# i2c-pressure-driver.net
KiCad netlist of a schematic drawn in EAGLE
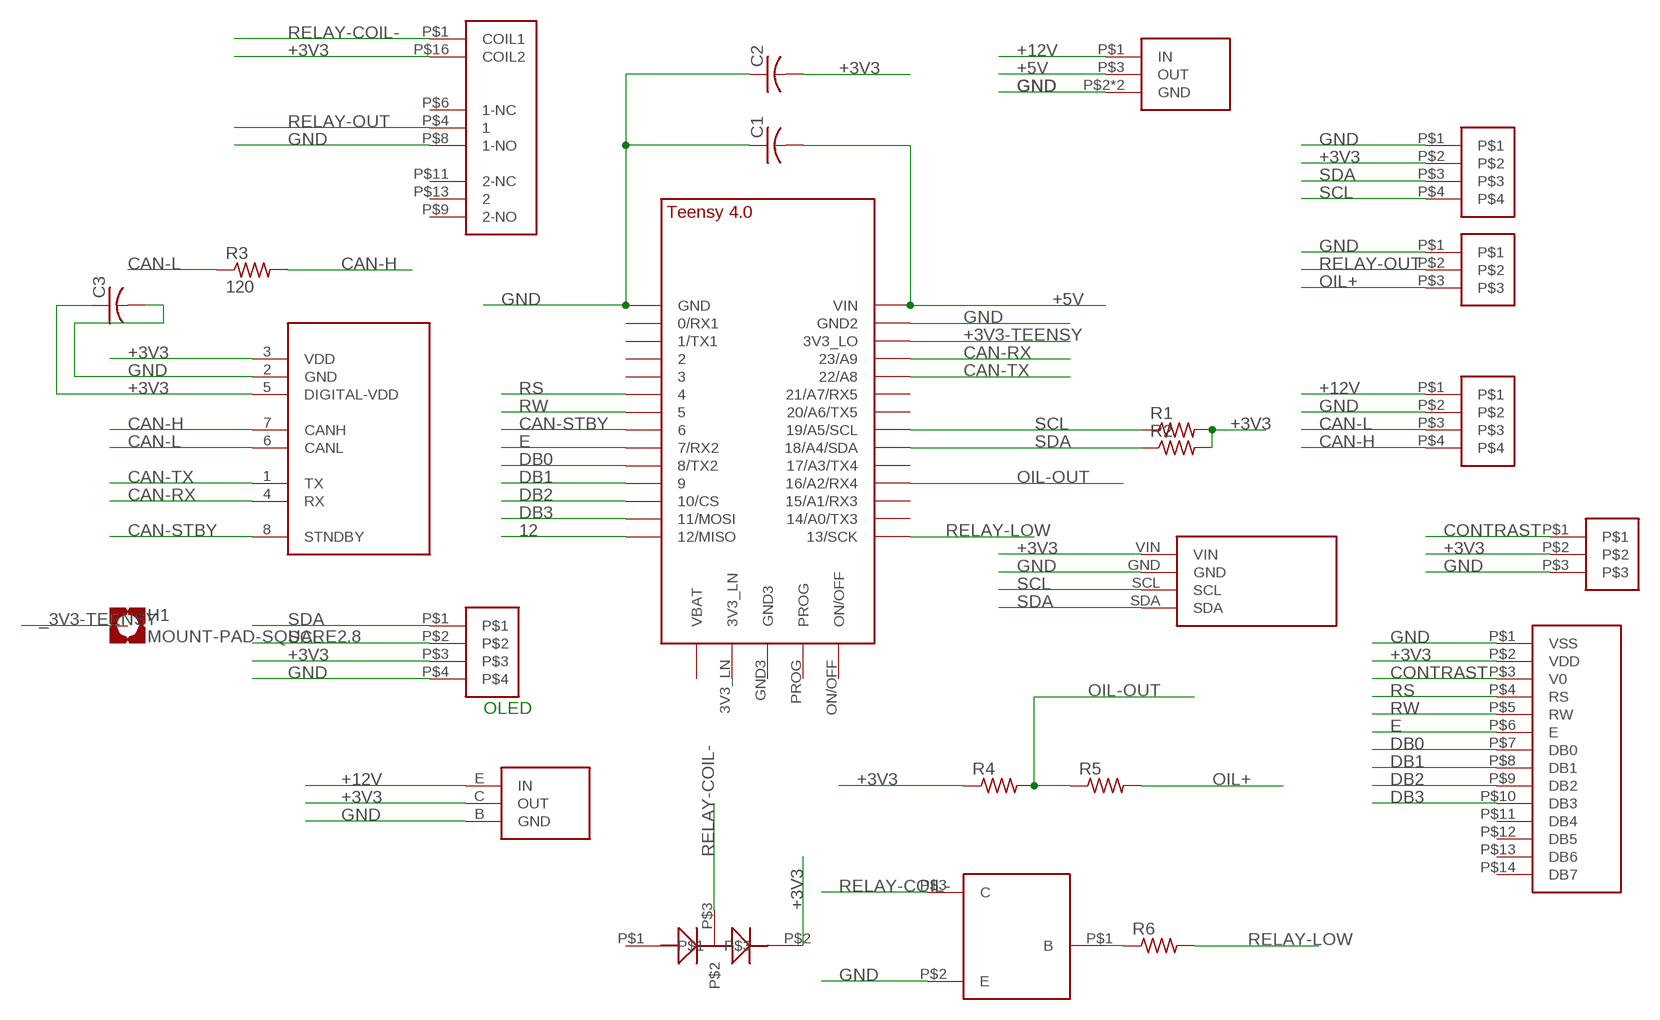
[diagram p0: schematic, sheet 1]

(export (version "E")
  (design (tool "Eeschema 10.0.6"))
  (components
    (comp (ref "C1")
      (value "C-USC1210K")
      (footprint "eagle-import:C1210K")
      (libsource (lib "eagle-import") (part "C-USC1210K"))
    )
    (comp (ref "C2")
      (value "C-USC1210K")
      (footprint "eagle-import:C1210K")
      (libsource (lib "eagle-import") (part "C-USC1210K"))
    )
    (comp (ref "C3")
      (value "C-USC0603K")
      (footprint "eagle-import:C0603K")
      (libsource (lib "eagle-import") (part "C-USC0603K"))
    )
    (comp (ref "H1")
      (value "MOUNT-PAD-SQUARE2.8")
      (footprint "eagle-import:2,8-PAD-SQUARE")
      (libsource (lib "eagle-import") (part "MOUNT-PAD-SQUARE2.8"))
    )
    (comp (ref "R1")
      (value "R-US_R0805")
      (footprint "eagle-import:R0805")
      (libsource (lib "eagle-import") (part "R-US_R0805"))
    )
    (comp (ref "R2")
      (value "R-US_R0805")
      (footprint "eagle-import:R0805")
      (libsource (lib "eagle-import") (part "R-US_R0805"))
    )
    (comp (ref "R3")
      (value "120")
      (footprint "eagle-import:R0805W")
      (libsource (lib "eagle-import") (part "R-US_R0805W"))
    )
    (comp (ref "R4")
      (value "R-US_M0805")
      (footprint "eagle-import:M0805")
      (libsource (lib "eagle-import") (part "R-US_M0805"))
    )
    (comp (ref "R5")
      (value "R-US_M0805")
      (footprint "eagle-import:M0805")
      (libsource (lib "eagle-import") (part "R-US_M0805"))
    )
    (comp (ref "R6")
      (value "R-US_R0805")
      (footprint "eagle-import:R0805")
      (libsource (lib "eagle-import") (part "R-US_R0805"))
    )
    (comp (ref "U$1")
      (value "TEENSY_4.0")
      (footprint "eagle-import:TEENSY_4.0")
      (libsource (lib "eagle-import") (part "TEENSY_4.0"))
    )
    (comp (ref "U$2")
      (value "NEWHAVEN-LCD-8X2")
      (footprint "eagle-import:NEWHAVEN-8X2-LCD")
      (libsource (lib "eagle-import") (part "NEWHAVEN-LCD-8X2"))
    )
    (comp (ref "U$3")
      (value "LDO-3.3V-AZ1117CR-3.3TRG1")
      (footprint "eagle-import:SOT89-BCE")
      (libsource (lib "eagle-import") (part "LDO-3.3V-AZ1117CR-3.3TRG1"))
    )
    (comp (ref "U$4")
      (value "1X4-1725672")
      (footprint "eagle-import:1X4-1725672")
      (libsource (lib "eagle-import") (part "1X4-1725672"))
    )
    (comp (ref "U$5")
      (value "1X3-1725669")
      (footprint "eagle-import:1X3-1725669")
      (libsource (lib "eagle-import") (part "1X3-1725669"))
    )
    (comp (ref "U$6")
      (value "1X4-1725672")
      (footprint "eagle-import:1X4-1725672")
      (libsource (lib "eagle-import") (part "1X4-1725672"))
    )
    (comp (ref "U$7")
      (value "MCP2562FD-CAN-TRANCIEVER")
      (footprint "eagle-import:SOIC8")
      (libsource (lib "eagle-import") (part "MCP2562FD-CAN-TRANCIEVER"))
    )
    (comp (ref "U$8")
      (value "TC33X-2-102E-POT")
      (footprint "eagle-import:TC33-X-2")
      (libsource (lib "eagle-import") (part "TC33X-2-102E-POT"))
    )
    (comp (ref "U$9")
      (value "1X4-1725672")
      (footprint "eagle-import:1X4-1725672")
      (libsource (lib "eagle-import") (part "1X4-1725672"))
    )
    (comp (ref "U$10")
      (value "LDO-5V-AZ1117CH2-5.0TRG1")
      (footprint "eagle-import:SOT-223")
      (libsource (lib "eagle-import") (part "LDO-5V-AZ1117CH2-5.0TRG1"))
    )
    (comp (ref "U$11")
      (value "BMP180-BREKOUT")
      (footprint "eagle-import:BMP180-BOARD")
      (libsource (lib "eagle-import") (part "BMP180-BREKOUT"))
    )
    (comp (ref "U$12")
      (value "RELAY-AMAZON")
      (footprint "eagle-import:RELAY-3V-AMAZON")
      (libsource (lib "eagle-import") (part "RELAY-AMAZON"))
    )
    (comp (ref "U$13")
      (value "NPN-GENERAL")
      (footprint "eagle-import:SOT23")
      (libsource (lib "eagle-import") (part "NPN-GENERAL"))
    )
    (comp (ref "U$14")
      (value "DIODE-MMBD4148SE")
      (footprint "eagle-import:SOT23")
      (libsource (lib "eagle-import") (part "DIODE-MMBD4148SE"))
    )
  )
  (nets
    (net (code "1") (name "/+3V3") (class "Default")
      (node (ref "C2") (pin "2") (pinfunction "2_2") (pintype "passive"))
      (node (ref "C3") (pin "1") (pinfunction "1_1") (pintype "passive"))
      (node (ref "R1") (pin "2") (pinfunction "2_2") (pintype "passive"))
      (node (ref "R2") (pin "2") (pinfunction "2_2") (pintype "passive"))
      (node (ref "R4") (pin "1") (pinfunction "1_1") (pintype "passive"))
      (node (ref "U$11") (pin "VIN") (pinfunction "VIN_VIN") (pintype "bidirectional"))
      (node (ref "U$12") (pin "P$16") (pinfunction "COIL2_P$16") (pintype "bidirectional"))
      (node (ref "U$14") (pin "P$2") (pinfunction "P$3_P$2") (pintype "bidirectional"))
      (node (ref "U$2") (pin "P$2") (pinfunction "VDD_P$2") (pintype "bidirectional"))
      (node (ref "U$3") (pin "C") (pinfunction "OUT_C") (pintype "bidirectional"))
      (node (ref "U$4") (pin "P$2") (pinfunction "P$2_P$2") (pintype "bidirectional"))
      (node (ref "U$7") (pin "3") (pinfunction "VDD_3") (pintype "bidirectional"))
      (node (ref "U$7") (pin "5") (pinfunction "DIGITAL-VDD_5") (pintype "bidirectional"))
      (node (ref "U$8") (pin "P$2") (pinfunction "P$2_P$2") (pintype "bidirectional"))
      (node (ref "U$9") (pin "P$3") (pinfunction "P$3_P$3") (pintype "bidirectional"))
    )
    (net (code "2") (name "/+3V3-TEENSY") (class "Default")
      (node (ref "U$1") (pin "3V3_LO") (pinfunction "3V3_LO_3V3_LO") (pintype "bidirectional"))
    )
    (net (code "3") (name "/+5V") (class "Default")
      (node (ref "C1") (pin "2") (pinfunction "2_2") (pintype "passive"))
      (node (ref "U$1") (pin "VIN") (pinfunction "VIN_VIN") (pintype "bidirectional"))
      (node (ref "U$10") (pin "P$3") (pinfunction "OUT_P$3") (pintype "bidirectional"))
    )
    (net (code "4") (name "/+12V") (class "Default")
      (node (ref "U$10") (pin "P$1") (pinfunction "IN_P$1") (pintype "bidirectional"))
      (node (ref "U$3") (pin "E") (pinfunction "IN_E") (pintype "bidirectional"))
      (node (ref "U$6") (pin "P$1") (pinfunction "P$1_P$1") (pintype "bidirectional"))
    )
    (net (code "5") (name "/12") (class "Default")
      (node (ref "U$1") (pin "12/MISO") (pinfunction "12/MISO_12/MISO") (pintype "bidirectional"))
    )
    (net (code "6") (name "/CAN-H") (class "Default")
      (node (ref "R3") (pin "2") (pinfunction "2_2") (pintype "passive"))
      (node (ref "U$6") (pin "P$4") (pinfunction "P$4_P$4") (pintype "bidirectional"))
      (node (ref "U$7") (pin "7") (pinfunction "CANH_7") (pintype "bidirectional"))
    )
    (net (code "7") (name "/CAN-L") (class "Default")
      (node (ref "R3") (pin "1") (pinfunction "1_1") (pintype "passive"))
      (node (ref "U$6") (pin "P$3") (pinfunction "P$3_P$3") (pintype "bidirectional"))
      (node (ref "U$7") (pin "6") (pinfunction "CANL_6") (pintype "bidirectional"))
    )
    (net (code "8") (name "/CAN-RX") (class "Default")
      (node (ref "U$1") (pin "23/A9") (pinfunction "23/A9_23/A9") (pintype "bidirectional"))
      (node (ref "U$7") (pin "4") (pinfunction "RX_4") (pintype "bidirectional"))
    )
    (net (code "9") (name "/CAN-STBY") (class "Default")
      (node (ref "U$1") (pin "6") (pinfunction "6_6") (pintype "bidirectional"))
      (node (ref "U$7") (pin "8") (pinfunction "STNDBY_8") (pintype "bidirectional"))
    )
    (net (code "10") (name "/CAN-TX") (class "Default")
      (node (ref "U$1") (pin "22/A8") (pinfunction "22/A8_22/A8") (pintype "bidirectional"))
      (node (ref "U$7") (pin "1") (pinfunction "TX_1") (pintype "bidirectional"))
    )
    (net (code "11") (name "/CONTRAST") (class "Default")
      (node (ref "U$2") (pin "P$3") (pinfunction "V0_P$3") (pintype "bidirectional"))
      (node (ref "U$8") (pin "P$1") (pinfunction "P$1_P$1") (pintype "bidirectional"))
    )
    (net (code "12") (name "/DB0") (class "Default")
      (node (ref "U$1") (pin "8") (pinfunction "8/TX2_8") (pintype "bidirectional"))
      (node (ref "U$2") (pin "P$7") (pinfunction "DB0_P$7") (pintype "bidirectional"))
    )
    (net (code "13") (name "/DB1") (class "Default")
      (node (ref "U$1") (pin "9/CS") (pinfunction "9_9/CS") (pintype "bidirectional"))
      (node (ref "U$2") (pin "P$8") (pinfunction "DB1_P$8") (pintype "bidirectional"))
    )
    (net (code "14") (name "/DB2") (class "Default")
      (node (ref "U$1") (pin "10/CS") (pinfunction "10/CS_10/CS") (pintype "bidirectional"))
      (node (ref "U$2") (pin "P$9") (pinfunction "DB2_P$9") (pintype "bidirectional"))
    )
    (net (code "15") (name "/DB3") (class "Default")
      (node (ref "U$1") (pin "11/MOSI") (pinfunction "11/MOSI_11/MOSI") (pintype "bidirectional"))
      (node (ref "U$2") (pin "P$10") (pinfunction "DB3_P$10") (pintype "bidirectional"))
    )
    (net (code "16") (name "/E") (class "Default")
      (node (ref "U$1") (pin "7") (pinfunction "7/RX2_7") (pintype "bidirectional"))
      (node (ref "U$2") (pin "P$6") (pinfunction "E_P$6") (pintype "bidirectional"))
    )
    (net (code "17") (name "/GND") (class "Default")
      (node (ref "C1") (pin "1") (pinfunction "1_1") (pintype "passive"))
      (node (ref "C2") (pin "1") (pinfunction "1_1") (pintype "passive"))
      (node (ref "C3") (pin "2") (pinfunction "2_2") (pintype "passive"))
      (node (ref "U$1") (pin "GND") (pinfunction "GND_GND") (pintype "bidirectional"))
      (node (ref "U$1") (pin "GND2") (pinfunction "GND2_GND2") (pintype "bidirectional"))
      (node (ref "U$10") (pin "P$2") (pinfunction "GND_P$2") (pintype "bidirectional"))
      (node (ref "U$10") (pin "PAD") (pinfunction "GND_PAD") (pintype "bidirectional"))
      (node (ref "U$11") (pin "GND") (pinfunction "GND_GND") (pintype "bidirectional"))
      (node (ref "U$12") (pin "P$8") (pinfunction "1-NO_P$8") (pintype "bidirectional"))
      (node (ref "U$13") (pin "P$2") (pinfunction "E_P$2") (pintype "bidirectional"))
      (node (ref "U$2") (pin "P$1") (pinfunction "VSS_P$1") (pintype "bidirectional"))
      (node (ref "U$3") (pin "B") (pinfunction "GND_B") (pintype "bidirectional"))
      (node (ref "U$4") (pin "P$1") (pinfunction "P$1_P$1") (pintype "bidirectional"))
      (node (ref "U$5") (pin "P$1") (pinfunction "P$1_P$1") (pintype "bidirectional"))
      (node (ref "U$6") (pin "P$2") (pinfunction "P$2_P$2") (pintype "bidirectional"))
      (node (ref "U$7") (pin "2") (pinfunction "GND_2") (pintype "bidirectional"))
      (node (ref "U$8") (pin "P$3") (pinfunction "P$3_P$3") (pintype "bidirectional"))
      (node (ref "U$9") (pin "P$4") (pinfunction "P$4_P$4") (pintype "bidirectional"))
    )
    (net (code "18") (name "/OIL+") (class "Default")
      (node (ref "R5") (pin "2") (pinfunction "2_2") (pintype "passive"))
      (node (ref "U$5") (pin "P$3") (pinfunction "P$3_P$3") (pintype "bidirectional"))
    )
    (net (code "19") (name "/OIL-OUT") (class "Default")
      (node (ref "R4") (pin "2") (pinfunction "2_2") (pintype "passive"))
      (node (ref "R5") (pin "1") (pinfunction "1_1") (pintype "passive"))
      (node (ref "U$1") (pin "16/A2") (pinfunction "16/A2/RX4_16/A2") (pintype "bidirectional"))
    )
    (net (code "20") (name "/RELAY-COIL-") (class "Default")
      (node (ref "U$12") (pin "P$1") (pinfunction "COIL1_P$1") (pintype "bidirectional"))
      (node (ref "U$13") (pin "P$3") (pinfunction "C_P$3") (pintype "bidirectional"))
      (node (ref "U$14") (pin "P$3") (pinfunction "P$2_P$3") (pintype "bidirectional"))
    )
    (net (code "21") (name "/RELAY-LOW") (class "Default")
      (node (ref "R6") (pin "2") (pinfunction "2_2") (pintype "passive"))
      (node (ref "U$1") (pin "13/SCK") (pinfunction "13/SCK_13/SCK") (pintype "bidirectional"))
    )
    (net (code "22") (name "/RELAY-OUT") (class "Default")
      (node (ref "U$12") (pin "P$4") (pinfunction "1_P$4") (pintype "bidirectional"))
      (node (ref "U$5") (pin "P$2") (pinfunction "P$2_P$2") (pintype "bidirectional"))
    )
    (net (code "23") (name "/RS") (class "Default")
      (node (ref "U$1") (pin "4/CANRX") (pinfunction "4_4/CANRX") (pintype "bidirectional"))
      (node (ref "U$2") (pin "P$4") (pinfunction "RS_P$4") (pintype "bidirectional"))
    )
    (net (code "24") (name "/RW") (class "Default")
      (node (ref "U$1") (pin "5") (pinfunction "5_5") (pintype "bidirectional"))
      (node (ref "U$2") (pin "P$5") (pinfunction "RW_P$5") (pintype "bidirectional"))
    )
    (net (code "25") (name "/SCL") (class "Default")
      (node (ref "R1") (pin "1") (pinfunction "1_1") (pintype "passive"))
      (node (ref "U$1") (pin "19/A5/SCL") (pinfunction "19/A5/SCL_19/A5/SCL") (pintype "bidirectional"))
      (node (ref "U$11") (pin "SCL") (pinfunction "SCL_SCL") (pintype "bidirectional"))
      (node (ref "U$4") (pin "P$4") (pinfunction "P$4_P$4") (pintype "bidirectional"))
      (node (ref "U$9") (pin "P$2") (pinfunction "P$2_P$2") (pintype "bidirectional"))
    )
    (net (code "26") (name "/SDA") (class "Default")
      (node (ref "R2") (pin "1") (pinfunction "1_1") (pintype "passive"))
      (node (ref "U$1") (pin "18/A4/SDA") (pinfunction "18/A4/SDA_18/A4/SDA") (pintype "bidirectional"))
      (node (ref "U$11") (pin "SDA") (pinfunction "SDA_SDA") (pintype "bidirectional"))
      (node (ref "U$4") (pin "P$3") (pinfunction "P$3_P$3") (pintype "bidirectional"))
      (node (ref "U$9") (pin "P$1") (pinfunction "P$1_P$1") (pintype "bidirectional"))
    )
    (net (code "27") (name "/_3V3-TEENSY") (class "Default")
      (node (ref "H1") (pin "B2,8") (pinfunction "MOUNT_B2,8") (pintype "passive"))
    )
    (net (code "28") (name "Net-(U$13-B)") (class "Default")
      (node (ref "R6") (pin "1") (pinfunction "1_1") (pintype "passive"))
      (node (ref "U$13") (pin "P$1") (pinfunction "B_P$1") (pintype "bidirectional"))
    )
    (net (code "29") (name "unconnected-(U$1-0{slash}RX1-Pad0{slash}RX)") (class "Default")
      (node (ref "U$1") (pin "0/RX") (pinfunction "0/RX1_0/RX") (pintype "bidirectional"))
    )
    (net (code "30") (name "unconnected-(U$1-1{slash}TX1-Pad1{slash}TX)") (class "Default")
      (node (ref "U$1") (pin "1/TX") (pinfunction "1/TX1_1/TX") (pintype "bidirectional"))
    )
    (net (code "31") (name "unconnected-(U$1-3-Pad3{slash}CANTX)") (class "Default")
      (node (ref "U$1") (pin "3/CANTX") (pinfunction "3_3/CANTX") (pintype "bidirectional"))
    )
    (net (code "32") (name "unconnected-(U$1-14{slash}A0{slash}TX3-Pad14{slash}A0)") (class "Default")
      (node (ref "U$1") (pin "14/A0") (pinfunction "14/A0/TX3_14/A0") (pintype "bidirectional"))
    )
    (net (code "33") (name "unconnected-(U$1-15{slash}A1{slash}RX3-Pad15{slash}A1)") (class "Default")
      (node (ref "U$1") (pin "15/A1") (pinfunction "15/A1/RX3_15/A1") (pintype "bidirectional"))
    )
    (net (code "34") (name "unconnected-(U$1-17{slash}A3{slash}TX4-Pad17{slash}A3)") (class "Default")
      (node (ref "U$1") (pin "17/A3") (pinfunction "17/A3/TX4_17/A3") (pintype "bidirectional"))
    )
    (net (code "35") (name "unconnected-(U$1-20{slash}A6{slash}TX5-Pad20{slash}A6)") (class "Default")
      (node (ref "U$1") (pin "20/A6") (pinfunction "20/A6/TX5_20/A6") (pintype "bidirectional"))
    )
    (net (code "36") (name "unconnected-(U$1-21{slash}A7{slash}RX5-Pad21{slash}A7)") (class "Default")
      (node (ref "U$1") (pin "21/A7") (pinfunction "21/A7/RX5_21/A7") (pintype "bidirectional"))
    )
    (net (code "37") (name "unconnected-(U$1-Pad2)") (class "Default")
      (node (ref "U$1") (pin "2") (pinfunction "2_2") (pintype "bidirectional"))
    )
    (net (code "38") (name "unconnected-(U$1-Pad3V3_LN)") (class "Default")
      (node (ref "U$1") (pin "3V3_LN") (pinfunction "3V3_LN_3V3_LN") (pintype "bidirectional"))
    )
    (net (code "39") (name "unconnected-(U$1-PadGND3)") (class "Default")
      (node (ref "U$1") (pin "GND3") (pinfunction "GND3_GND3") (pintype "bidirectional"))
    )
    (net (code "40") (name "unconnected-(U$1-PadON{slash}OFF)") (class "Default")
      (node (ref "U$1") (pin "ON/OFF") (pinfunction "ON/OFF_ON/OFF") (pintype "bidirectional"))
    )
    (net (code "41") (name "unconnected-(U$1-PadPROG)") (class "Default")
      (node (ref "U$1") (pin "PROG") (pinfunction "PROG_PROG") (pintype "bidirectional"))
    )
    (net (code "42") (name "unconnected-(U$1-VBAT-PadVBAT\\)") (class "Default")
      (node (ref "U$1") (pin "VBAT\\") (pinfunction "VBAT_VBAT\\") (pintype "bidirectional"))
    )
    (net (code "43") (name "unconnected-(U$2-DB4-PadP$11)") (class "Default")
      (node (ref "U$2") (pin "P$11") (pinfunction "DB4_P$11") (pintype "bidirectional"))
    )
    (net (code "44") (name "unconnected-(U$2-DB5-PadP$12)") (class "Default")
      (node (ref "U$2") (pin "P$12") (pinfunction "DB5_P$12") (pintype "bidirectional"))
    )
    (net (code "45") (name "unconnected-(U$2-DB6-PadP$13)") (class "Default")
      (node (ref "U$2") (pin "P$13") (pinfunction "DB6_P$13") (pintype "bidirectional"))
    )
    (net (code "46") (name "unconnected-(U$2-DB7-PadP$14)") (class "Default")
      (node (ref "U$2") (pin "P$14") (pinfunction "DB7_P$14") (pintype "bidirectional"))
    )
    (net (code "47") (name "unconnected-(U$12-1-NC-PadP$6)") (class "Default")
      (node (ref "U$12") (pin "P$6") (pinfunction "1-NC_P$6") (pintype "bidirectional"))
    )
    (net (code "48") (name "unconnected-(U$12-2-NC-PadP$11)") (class "Default")
      (node (ref "U$12") (pin "P$11") (pinfunction "2-NC_P$11") (pintype "bidirectional"))
    )
    (net (code "49") (name "unconnected-(U$12-2-NO-PadP$9)") (class "Default")
      (node (ref "U$12") (pin "P$9") (pinfunction "2-NO_P$9") (pintype "bidirectional"))
    )
    (net (code "50") (name "unconnected-(U$12-2-PadP$13)") (class "Default")
      (node (ref "U$12") (pin "P$13") (pinfunction "2_P$13") (pintype "bidirectional"))
    )
    (net (code "51") (name "unconnected-(U$14-PadP$1)") (class "Default")
      (node (ref "U$14") (pin "P$1") (pinfunction "P$1_P$1") (pintype "bidirectional"))
    )
  )
)
